# 19_RK3568_Audio_Interface.net
KiCad netlist of a schematic drawn in Altium Designer
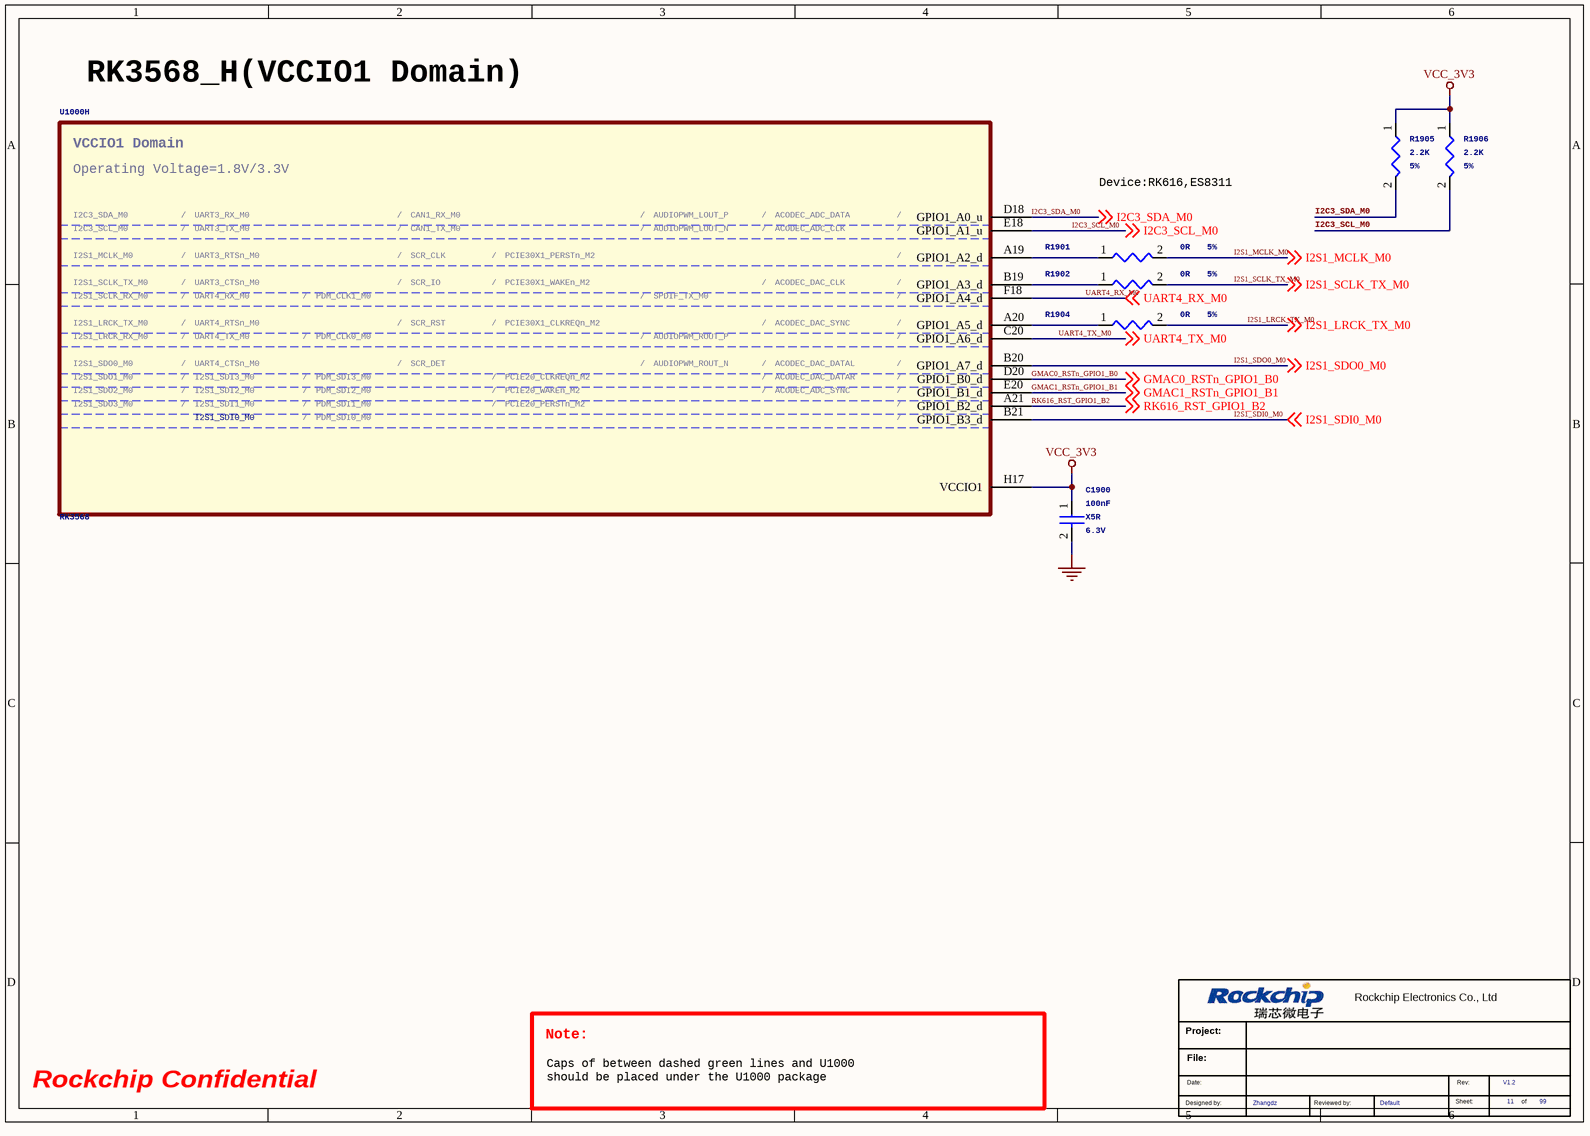
[diagram p0: 19.RK3568_Audio Interface.SchDoc]

(export (version "E")
  (design (tool "Eeschema 10.0.6"))
  (components
    (comp (ref "*")
      (value "Rockchip_new")
      (fields
        (field (name "SCHEMATIC PAGE COUNT") "99")
        (field (name "SCHEMATIC PAGE NUMBER") "11")
        (field (name "DESIGNER") "Zhangdz")
        (field (name "REVISION") "V1.2")
        (field (name "CHECK") "Default")
      )
      (libsource (lib "*") (part "Rockchip_new"))
    )
    (comp (ref "C1900")
      (value "100nF")
      (footprint "C0201")
      (description "cap,100.00nF,+/-10%,6.3V,X5R,C0201")
      (fields
        (field (name "VOLTAGE") "6.3V")
        (field (name "DIELECTRIC") "X5R")
        (field (name "TOLERANCE") "10%")
        (field (name "MANUFACTURER") "TDK")
        (field (name "CREATED BY") "JJJ")
      )
      (libsource (lib "*") (part "CAP NP"))
    )
    (comp (ref "R1901")
      (value "0R")
      (footprint "R0402")
      (description "通用厚膜电阻,0R,+/-5%,R0402,1/16W.")
      (fields
        (field (name "TOLERANCE") "5%")
        (field (name "MANUFACTURER") "YAGEO")
        (field (name "CREATED BY") "YTL")
      )
      (libsource (lib "*") (part "RESISTOR"))
    )
    (comp (ref "R1902")
      (value "0R")
      (footprint "R0402")
      (description "通用厚膜电阻,0R,+/-5%,R0402,1/16W.")
      (fields
        (field (name "TOLERANCE") "5%")
        (field (name "MANUFACTURER") "YAGEO")
        (field (name "CREATED BY") "YTL")
      )
      (libsource (lib "*") (part "RESISTOR"))
    )
    (comp (ref "R1904")
      (value "0R")
      (footprint "R0402")
      (description "通用厚膜电阻,0R,+/-5%,R0402,1/16W.")
      (fields
        (field (name "TOLERANCE") "5%")
        (field (name "MANUFACTURER") "YAGEO")
        (field (name "CREATED BY") "YTL")
      )
      (libsource (lib "*") (part "RESISTOR"))
    )
    (comp (ref "R1905")
      (value "2.2K")
      (footprint "R0402")
      (description "通用厚膜电阻,2K2,+/-5%,R0402,1/16W.")
      (fields
        (field (name "TOLERANCE") "5%")
        (field (name "MANUFACTURER") "YAGEO")
        (field (name "CREATED BY") "YTL")
      )
      (libsource (lib "*") (part "RESISTOR"))
    )
    (comp (ref "R1906")
      (value "2.2K")
      (footprint "R0402")
      (description "通用厚膜电阻,2K2,+/-5%,R0402,1/16W.")
      (fields
        (field (name "TOLERANCE") "5%")
        (field (name "MANUFACTURER") "YAGEO")
        (field (name "CREATED BY") "YTL")
      )
      (libsource (lib "*") (part "RESISTOR"))
    )
    (comp (ref "U1000")
      (value "RK3568")
      (footprint "BGA636_19R00X19R00X1R20")
      (description "ROCKCHIP SOC")
      (fields (field (name "MANUFACTURER") "Rockchip (瑞芯微)") (field (name "CREATED BY") "JJJ"))
      (libsource (lib "*") (part "SOC_RK3568"))
    )
  )
  (nets
    (net (code "1") (name "GMAC0_RSTn_GPIO1_B0") (class "Default")
      (node (ref "U1000") (pin "D20") (pinfunction "GPIO1_B0_d_D20") (pintype "passive"))
    )
    (net (code "2") (name "GMAC1_RSTn_GPIO1_B1") (class "Default")
      (node (ref "U1000") (pin "E20") (pinfunction "GPIO1_B1_d_E20") (pintype "passive"))
    )
    (net (code "3") (name "GND") (class "Default")
      (node (ref "C1900") (pin "2") (pinfunction "2_2") (pintype "passive"))
    )
    (net (code "4") (name "I2C3_SCL_M0") (class "Default")
      (node (ref "R1906") (pin "2") (pinfunction "2_2") (pintype "passive"))
      (node (ref "U1000") (pin "E18") (pinfunction "GPIO1_A1_u_E18") (pintype "passive"))
    )
    (net (code "5") (name "I2C3_SDA_M0") (class "Default")
      (node (ref "R1905") (pin "2") (pinfunction "2_2") (pintype "passive"))
      (node (ref "U1000") (pin "D18") (pinfunction "GPIO1_A0_u_D18") (pintype "passive"))
    )
    (net (code "6") (name "I2S1_LRCK_TX_M0") (class "Default")
      (node (ref "R1904") (pin "2") (pinfunction "2_2") (pintype "passive"))
    )
    (net (code "7") (name "I2S1_MCLK_M0") (class "Default")
      (node (ref "R1901") (pin "2") (pinfunction "2_2") (pintype "passive"))
    )
    (net (code "8") (name "I2S1_SCLK_TX_M0") (class "Default")
      (node (ref "R1902") (pin "2") (pinfunction "2_2") (pintype "passive"))
    )
    (net (code "9") (name "I2S1_SDI0_M0") (class "Default")
      (node (ref "U1000") (pin "B21") (pinfunction "GPIO1_B3_d_B21") (pintype "passive"))
    )
    (net (code "10") (name "I2S1_SDO0_M0") (class "Default")
      (node (ref "U1000") (pin "B20") (pinfunction "GPIO1_A7_d_B20") (pintype "passive"))
    )
    (net (code "11") (name "Net-(U1000H-GPIO1_A2_d)") (class "Default")
      (node (ref "R1901") (pin "1") (pinfunction "1_1") (pintype "passive"))
      (node (ref "U1000") (pin "A19") (pinfunction "GPIO1_A2_d_A19") (pintype "passive"))
    )
    (net (code "12") (name "Net-(U1000H-GPIO1_A3_d)") (class "Default")
      (node (ref "R1902") (pin "1") (pinfunction "1_1") (pintype "passive"))
      (node (ref "U1000") (pin "B19") (pinfunction "GPIO1_A3_d_B19") (pintype "passive"))
    )
    (net (code "13") (name "Net-(U1000H-GPIO1_A5_d)") (class "Default")
      (node (ref "R1904") (pin "1") (pinfunction "1_1") (pintype "passive"))
      (node (ref "U1000") (pin "A20") (pinfunction "GPIO1_A5_d_A20") (pintype "passive"))
    )
    (net (code "14") (name "RK616_RST_GPIO1_B2") (class "Default")
      (node (ref "U1000") (pin "A21") (pinfunction "GPIO1_B2_d_A21") (pintype "passive"))
    )
    (net (code "15") (name "UART4_RX_M0") (class "Default")
      (node (ref "U1000") (pin "F18") (pinfunction "GPIO1_A4_d_F18") (pintype "passive"))
    )
    (net (code "16") (name "UART4_TX_M0") (class "Default")
      (node (ref "U1000") (pin "C20") (pinfunction "GPIO1_A6_d_C20") (pintype "passive"))
    )
    (net (code "17") (name "VCC_3V3") (class "Default")
      (node (ref "C1900") (pin "1") (pinfunction "1_1") (pintype "passive"))
      (node (ref "R1905") (pin "1") (pinfunction "1_1") (pintype "passive"))
      (node (ref "R1906") (pin "1") (pinfunction "1_1") (pintype "passive"))
      (node (ref "U1000") (pin "H17") (pinfunction "VCCIO1_H17") (pintype "passive"))
    )
  )
)
